# MB_ANALOG.net
KiCad netlist of a schematic drawn in Altium Designer
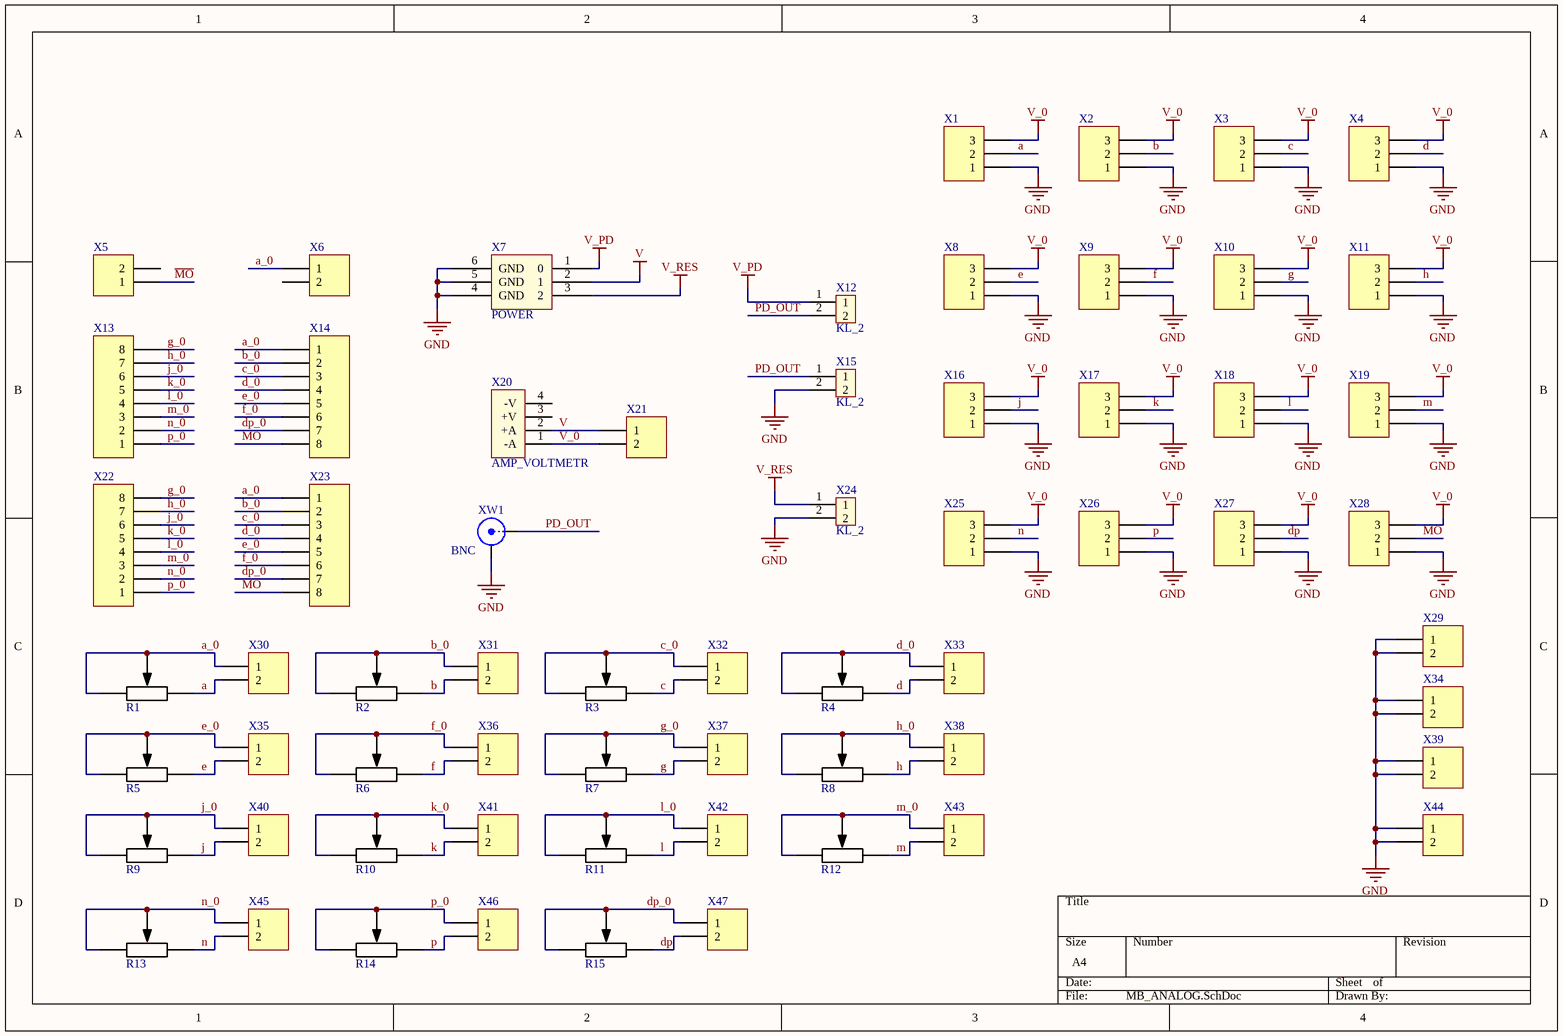
[diagram p0: MB_ANALOG.SchDoc]

(export (version "E")
  (design (tool "Eeschema 10.0.6"))
  (components
    (comp (ref "R1")
      (value "RES 3266W")
      (footprint "RES 3266W")
      (libsource (lib "msp_SchLib") (part "RES 3266W"))
    )
    (comp (ref "R2")
      (value "RES 3266W")
      (footprint "RES 3266W")
      (libsource (lib "msp_SchLib") (part "RES 3266W"))
    )
    (comp (ref "R3")
      (value "RES 3266W")
      (footprint "RES 3266W")
      (libsource (lib "msp_SchLib") (part "RES 3266W"))
    )
    (comp (ref "R4")
      (value "RES 3266W")
      (footprint "RES 3266W")
      (libsource (lib "msp_SchLib") (part "RES 3266W"))
    )
    (comp (ref "R5")
      (value "RES 3266W")
      (footprint "RES 3266W")
      (libsource (lib "msp_SchLib") (part "RES 3266W"))
    )
    (comp (ref "R6")
      (value "RES 3266W")
      (footprint "RES 3266W")
      (libsource (lib "msp_SchLib") (part "RES 3266W"))
    )
    (comp (ref "R7")
      (value "RES 3266W")
      (footprint "RES 3266W")
      (libsource (lib "msp_SchLib") (part "RES 3266W"))
    )
    (comp (ref "R8")
      (value "RES 3266W")
      (footprint "RES 3266W")
      (libsource (lib "msp_SchLib") (part "RES 3266W"))
    )
    (comp (ref "R9")
      (value "RES 3266W")
      (footprint "RES 3266W")
      (libsource (lib "msp_SchLib") (part "RES 3266W"))
    )
    (comp (ref "R10")
      (value "RES 3266W")
      (footprint "RES 3266W")
      (libsource (lib "msp_SchLib") (part "RES 3266W"))
    )
    (comp (ref "R11")
      (value "RES 3266W")
      (footprint "RES 3266W")
      (libsource (lib "msp_SchLib") (part "RES 3266W"))
    )
    (comp (ref "R12")
      (value "RES 3266W")
      (footprint "RES 3266W")
      (libsource (lib "msp_SchLib") (part "RES 3266W"))
    )
    (comp (ref "R13")
      (value "RES 3266W")
      (footprint "RES 3266W")
      (libsource (lib "msp_SchLib") (part "RES 3266W"))
    )
    (comp (ref "R14")
      (value "RES 3266W")
      (footprint "RES 3266W")
      (libsource (lib "msp_SchLib") (part "RES 3266W"))
    )
    (comp (ref "R15")
      (value "RES 3266W")
      (footprint "RES 3266W")
      (libsource (lib "msp_SchLib") (part "RES 3266W"))
    )
    (comp (ref "X1")
      (value "Header 3")
      (footprint "HDR1X3")
      (description "Header, 3-Pin")
      (fields (field (name "PUBLISHER") "Altium Limited"))
      (libsource (lib "Miscellaneous Connectors") (part "Header 3"))
    )
    (comp (ref "X2")
      (value "Header 3")
      (footprint "HDR1X3")
      (description "Header, 3-Pin")
      (fields (field (name "PUBLISHER") "Altium Limited"))
      (libsource (lib "Miscellaneous Connectors") (part "Header 3"))
    )
    (comp (ref "X3")
      (value "Header 3")
      (footprint "HDR1X3")
      (description "Header, 3-Pin")
      (fields (field (name "PUBLISHER") "Altium Limited"))
      (libsource (lib "Miscellaneous Connectors") (part "Header 3"))
    )
    (comp (ref "X4")
      (value "Header 3")
      (footprint "HDR1X3")
      (description "Header, 3-Pin")
      (fields (field (name "PUBLISHER") "Altium Limited"))
      (libsource (lib "Miscellaneous Connectors") (part "Header 3"))
    )
    (comp (ref "X5")
      (value "Header 2")
      (footprint "HDR1X2")
      (description "Header, 2-Pin")
      (fields (field (name "PUBLISHER") "Altium Limited"))
      (libsource (lib "") (part "Header 2_1"))
    )
    (comp (ref "X6")
      (value "Header 2")
      (footprint "HDR1X2")
      (description "Header, 2-Pin")
      (fields (field (name "PUBLISHER") "Altium Limited"))
      (libsource (lib "Miscellaneous Connectors") (part "Header 2"))
    )
    (comp (ref "X7") (value "POWER") (footprint "POWER") (libsource (lib "msp_SchLib") (part "POWER")))
    (comp (ref "X8")
      (value "Header 3")
      (footprint "HDR1X3")
      (description "Header, 3-Pin")
      (fields (field (name "PUBLISHER") "Altium Limited"))
      (libsource (lib "Miscellaneous Connectors") (part "Header 3"))
    )
    (comp (ref "X9")
      (value "Header 3")
      (footprint "HDR1X3")
      (description "Header, 3-Pin")
      (fields (field (name "PUBLISHER") "Altium Limited"))
      (libsource (lib "Miscellaneous Connectors") (part "Header 3"))
    )
    (comp (ref "X10")
      (value "Header 3")
      (footprint "HDR1X3")
      (description "Header, 3-Pin")
      (fields (field (name "PUBLISHER") "Altium Limited"))
      (libsource (lib "Miscellaneous Connectors") (part "Header 3"))
    )
    (comp (ref "X11")
      (value "Header 3")
      (footprint "HDR1X3")
      (description "Header, 3-Pin")
      (fields (field (name "PUBLISHER") "Altium Limited"))
      (libsource (lib "Miscellaneous Connectors") (part "Header 3"))
    )
    (comp (ref "X12")
      (value "KL_2")
      (footprint "KLEMMNIK_2")
      (libsource (lib "vpl_Schlib") (part "KLEMMNIK_2"))
    )
    (comp (ref "X13")
      (value "Header 8")
      (footprint "HDR1X8")
      (description "Header, 8-Pin")
      (fields (field (name "PUBLISHER") "Altium Limited"))
      (libsource (lib "") (part "Header 8_1"))
    )
    (comp (ref "X14")
      (value "Header 8")
      (footprint "HDR1X8")
      (description "Header, 8-Pin")
      (fields (field (name "PUBLISHER") "Altium Limited"))
      (libsource (lib "Miscellaneous Connectors") (part "Header 8"))
    )
    (comp (ref "X15")
      (value "KL_2")
      (footprint "KLEMMNIK_2")
      (libsource (lib "vpl_Schlib") (part "KLEMMNIK_2"))
    )
    (comp (ref "X16")
      (value "Header 3")
      (footprint "HDR1X3")
      (description "Header, 3-Pin")
      (fields (field (name "PUBLISHER") "Altium Limited"))
      (libsource (lib "Miscellaneous Connectors") (part "Header 3"))
    )
    (comp (ref "X17")
      (value "Header 3")
      (footprint "HDR1X3")
      (description "Header, 3-Pin")
      (fields (field (name "PUBLISHER") "Altium Limited"))
      (libsource (lib "Miscellaneous Connectors") (part "Header 3"))
    )
    (comp (ref "X18")
      (value "Header 3")
      (footprint "HDR1X3")
      (description "Header, 3-Pin")
      (fields (field (name "PUBLISHER") "Altium Limited"))
      (libsource (lib "Miscellaneous Connectors") (part "Header 3"))
    )
    (comp (ref "X19")
      (value "Header 3")
      (footprint "HDR1X3")
      (description "Header, 3-Pin")
      (fields (field (name "PUBLISHER") "Altium Limited"))
      (libsource (lib "Miscellaneous Connectors") (part "Header 3"))
    )
    (comp (ref "X20")
      (value "AMP_VOLTMETR")
      (footprint "AMP_VOLTMETR")
      (libsource (lib "msp_SchLib") (part "AMP_VOLTMETR"))
    )
    (comp (ref "X21")
      (value "Header 2")
      (footprint "HDR1X2")
      (description "Header, 2-Pin")
      (fields (field (name "PUBLISHER") "Altium Limited"))
      (libsource (lib "Miscellaneous Connectors") (part "Header 2"))
    )
    (comp (ref "X22")
      (value "Header 8")
      (footprint "HDR1X8")
      (description "Header, 8-Pin")
      (fields (field (name "PUBLISHER") "Altium Limited"))
      (libsource (lib "") (part "Header 8_1"))
    )
    (comp (ref "X23")
      (value "Header 8")
      (footprint "HDR1X8")
      (description "Header, 8-Pin")
      (fields (field (name "PUBLISHER") "Altium Limited"))
      (libsource (lib "Miscellaneous Connectors") (part "Header 8"))
    )
    (comp (ref "X24")
      (value "KL_2")
      (footprint "KLEMMNIK_2")
      (libsource (lib "vpl_Schlib") (part "KLEMMNIK_2"))
    )
    (comp (ref "X25")
      (value "Header 3")
      (footprint "HDR1X3")
      (description "Header, 3-Pin")
      (fields (field (name "PUBLISHER") "Altium Limited"))
      (libsource (lib "Miscellaneous Connectors") (part "Header 3"))
    )
    (comp (ref "X26")
      (value "Header 3")
      (footprint "HDR1X3")
      (description "Header, 3-Pin")
      (fields (field (name "PUBLISHER") "Altium Limited"))
      (libsource (lib "Miscellaneous Connectors") (part "Header 3"))
    )
    (comp (ref "X27")
      (value "Header 3")
      (footprint "HDR1X3")
      (description "Header, 3-Pin")
      (fields (field (name "PUBLISHER") "Altium Limited"))
      (libsource (lib "Miscellaneous Connectors") (part "Header 3"))
    )
    (comp (ref "X28")
      (value "Header 3")
      (footprint "HDR1X3")
      (description "Header, 3-Pin")
      (fields (field (name "PUBLISHER") "Altium Limited"))
      (libsource (lib "Miscellaneous Connectors") (part "Header 3"))
    )
    (comp (ref "X29")
      (value "Header 2")
      (footprint "HDR1X2")
      (description "Header, 2-Pin")
      (fields (field (name "PUBLISHER") "Altium Limited"))
      (libsource (lib "Miscellaneous Connectors") (part "Header 2"))
    )
    (comp (ref "X30")
      (value "Header 2")
      (footprint "HDR1X2")
      (description "Header, 2-Pin")
      (fields (field (name "PUBLISHER") "Altium Limited"))
      (libsource (lib "Miscellaneous Connectors") (part "Header 2"))
    )
    (comp (ref "X31")
      (value "Header 2")
      (footprint "HDR1X2")
      (description "Header, 2-Pin")
      (fields (field (name "PUBLISHER") "Altium Limited"))
      (libsource (lib "Miscellaneous Connectors") (part "Header 2"))
    )
    (comp (ref "X32")
      (value "Header 2")
      (footprint "HDR1X2")
      (description "Header, 2-Pin")
      (fields (field (name "PUBLISHER") "Altium Limited"))
      (libsource (lib "Miscellaneous Connectors") (part "Header 2"))
    )
    (comp (ref "X33")
      (value "Header 2")
      (footprint "HDR1X2")
      (description "Header, 2-Pin")
      (fields (field (name "PUBLISHER") "Altium Limited"))
      (libsource (lib "Miscellaneous Connectors") (part "Header 2"))
    )
    (comp (ref "X34")
      (value "Header 2")
      (footprint "HDR1X2")
      (description "Header, 2-Pin")
      (fields (field (name "PUBLISHER") "Altium Limited"))
      (libsource (lib "Miscellaneous Connectors") (part "Header 2"))
    )
    (comp (ref "X35")
      (value "Header 2")
      (footprint "HDR1X2")
      (description "Header, 2-Pin")
      (fields (field (name "PUBLISHER") "Altium Limited"))
      (libsource (lib "Miscellaneous Connectors") (part "Header 2"))
    )
    (comp (ref "X36")
      (value "Header 2")
      (footprint "HDR1X2")
      (description "Header, 2-Pin")
      (fields (field (name "PUBLISHER") "Altium Limited"))
      (libsource (lib "Miscellaneous Connectors") (part "Header 2"))
    )
    (comp (ref "X37")
      (value "Header 2")
      (footprint "HDR1X2")
      (description "Header, 2-Pin")
      (fields (field (name "PUBLISHER") "Altium Limited"))
      (libsource (lib "Miscellaneous Connectors") (part "Header 2"))
    )
    (comp (ref "X38")
      (value "Header 2")
      (footprint "HDR1X2")
      (description "Header, 2-Pin")
      (fields (field (name "PUBLISHER") "Altium Limited"))
      (libsource (lib "Miscellaneous Connectors") (part "Header 2"))
    )
    (comp (ref "X39")
      (value "Header 2")
      (footprint "HDR1X2")
      (description "Header, 2-Pin")
      (fields (field (name "PUBLISHER") "Altium Limited"))
      (libsource (lib "Miscellaneous Connectors") (part "Header 2"))
    )
    (comp (ref "X40")
      (value "Header 2")
      (footprint "HDR1X2")
      (description "Header, 2-Pin")
      (fields (field (name "PUBLISHER") "Altium Limited"))
      (libsource (lib "Miscellaneous Connectors") (part "Header 2"))
    )
    (comp (ref "X41")
      (value "Header 2")
      (footprint "HDR1X2")
      (description "Header, 2-Pin")
      (fields (field (name "PUBLISHER") "Altium Limited"))
      (libsource (lib "Miscellaneous Connectors") (part "Header 2"))
    )
    (comp (ref "X42")
      (value "Header 2")
      (footprint "HDR1X2")
      (description "Header, 2-Pin")
      (fields (field (name "PUBLISHER") "Altium Limited"))
      (libsource (lib "Miscellaneous Connectors") (part "Header 2"))
    )
    (comp (ref "X43")
      (value "Header 2")
      (footprint "HDR1X2")
      (description "Header, 2-Pin")
      (fields (field (name "PUBLISHER") "Altium Limited"))
      (libsource (lib "Miscellaneous Connectors") (part "Header 2"))
    )
    (comp (ref "X44")
      (value "Header 2")
      (footprint "HDR1X2")
      (description "Header, 2-Pin")
      (fields (field (name "PUBLISHER") "Altium Limited"))
      (libsource (lib "Miscellaneous Connectors") (part "Header 2"))
    )
    (comp (ref "X45")
      (value "Header 2")
      (footprint "HDR1X2")
      (description "Header, 2-Pin")
      (fields (field (name "PUBLISHER") "Altium Limited"))
      (libsource (lib "Miscellaneous Connectors") (part "Header 2"))
    )
    (comp (ref "X46")
      (value "Header 2")
      (footprint "HDR1X2")
      (description "Header, 2-Pin")
      (fields (field (name "PUBLISHER") "Altium Limited"))
      (libsource (lib "Miscellaneous Connectors") (part "Header 2"))
    )
    (comp (ref "X47")
      (value "Header 2")
      (footprint "HDR1X2")
      (description "Header, 2-Pin")
      (fields (field (name "PUBLISHER") "Altium Limited"))
      (libsource (lib "Miscellaneous Connectors") (part "Header 2"))
    )
    (comp (ref "XW1")
      (value "BNC")
      (footprint "BNC_RA CON")
      (description "BNC Elbow Connector")
      (fields (field (name "PUBLISHER") "Altium Limited"))
      (libsource (lib "Miscellaneous Connectors") (part "BNC"))
    )
  )
  (nets
    (net (code "1") (name "/PD_OUT") (class "Default")
      (node (ref "X12") (pin "2") (pinfunction "2_2") (pintype "passive"))
      (node (ref "X15") (pin "1") (pinfunction "1_1") (pintype "passive"))
      (node (ref "XW1") (pin "1") (pinfunction "X_1") (pintype "passive"))
    )
    (net (code "2") (name "/a") (class "Default")
      (node (ref "R1") (pin "3") (pinfunction "3_3") (pintype "passive"))
      (node (ref "X1") (pin "2") (pinfunction "2_2") (pintype "passive"))
      (node (ref "X30") (pin "2") (pinfunction "2_2") (pintype "passive"))
    )
    (net (code "3") (name "/a_0") (class "Default")
      (node (ref "R1") (pin "1") (pinfunction "1_1") (pintype "passive"))
      (node (ref "R1") (pin "2") (pinfunction "2_2") (pintype "passive"))
      (node (ref "X14") (pin "1") (pinfunction "1_1") (pintype "passive"))
      (node (ref "X23") (pin "1") (pinfunction "1_1") (pintype "passive"))
      (node (ref "X30") (pin "1") (pinfunction "1_1") (pintype "passive"))
      (node (ref "X6") (pin "1") (pinfunction "1_1") (pintype "passive"))
    )
    (net (code "4") (name "/b") (class "Default")
      (node (ref "R2") (pin "3") (pinfunction "3_3") (pintype "passive"))
      (node (ref "X2") (pin "2") (pinfunction "2_2") (pintype "passive"))
      (node (ref "X31") (pin "2") (pinfunction "2_2") (pintype "passive"))
    )
    (net (code "5") (name "/b_0") (class "Default")
      (node (ref "R2") (pin "1") (pinfunction "1_1") (pintype "passive"))
      (node (ref "R2") (pin "2") (pinfunction "2_2") (pintype "passive"))
      (node (ref "X14") (pin "2") (pinfunction "2_2") (pintype "passive"))
      (node (ref "X23") (pin "2") (pinfunction "2_2") (pintype "passive"))
      (node (ref "X31") (pin "1") (pinfunction "1_1") (pintype "passive"))
    )
    (net (code "6") (name "/c") (class "Default")
      (node (ref "R3") (pin "3") (pinfunction "3_3") (pintype "passive"))
      (node (ref "X3") (pin "2") (pinfunction "2_2") (pintype "passive"))
      (node (ref "X32") (pin "2") (pinfunction "2_2") (pintype "passive"))
    )
    (net (code "7") (name "/c_0") (class "Default")
      (node (ref "R3") (pin "1") (pinfunction "1_1") (pintype "passive"))
      (node (ref "R3") (pin "2") (pinfunction "2_2") (pintype "passive"))
      (node (ref "X14") (pin "3") (pinfunction "3_3") (pintype "passive"))
      (node (ref "X23") (pin "3") (pinfunction "3_3") (pintype "passive"))
      (node (ref "X32") (pin "1") (pinfunction "1_1") (pintype "passive"))
    )
    (net (code "8") (name "/d") (class "Default")
      (node (ref "R4") (pin "3") (pinfunction "3_3") (pintype "passive"))
      (node (ref "X33") (pin "2") (pinfunction "2_2") (pintype "passive"))
      (node (ref "X4") (pin "2") (pinfunction "2_2") (pintype "passive"))
    )
    (net (code "9") (name "/d_0") (class "Default")
      (node (ref "R4") (pin "1") (pinfunction "1_1") (pintype "passive"))
      (node (ref "R4") (pin "2") (pinfunction "2_2") (pintype "passive"))
      (node (ref "X14") (pin "4") (pinfunction "4_4") (pintype "passive"))
      (node (ref "X23") (pin "4") (pinfunction "4_4") (pintype "passive"))
      (node (ref "X33") (pin "1") (pinfunction "1_1") (pintype "passive"))
    )
    (net (code "10") (name "/dp") (class "Default")
      (node (ref "R15") (pin "3") (pinfunction "3_3") (pintype "passive"))
      (node (ref "X27") (pin "2") (pinfunction "2_2") (pintype "passive"))
      (node (ref "X47") (pin "2") (pinfunction "2_2") (pintype "passive"))
    )
    (net (code "11") (name "/dp_0") (class "Default")
      (node (ref "R15") (pin "1") (pinfunction "1_1") (pintype "passive"))
      (node (ref "R15") (pin "2") (pinfunction "2_2") (pintype "passive"))
      (node (ref "X14") (pin "7") (pinfunction "7_7") (pintype "passive"))
      (node (ref "X23") (pin "7") (pinfunction "7_7") (pintype "passive"))
      (node (ref "X47") (pin "1") (pinfunction "1_1") (pintype "passive"))
    )
    (net (code "12") (name "/e") (class "Default")
      (node (ref "R5") (pin "3") (pinfunction "3_3") (pintype "passive"))
      (node (ref "X35") (pin "2") (pinfunction "2_2") (pintype "passive"))
      (node (ref "X8") (pin "2") (pinfunction "2_2") (pintype "passive"))
    )
    (net (code "13") (name "/e_0") (class "Default")
      (node (ref "R5") (pin "1") (pinfunction "1_1") (pintype "passive"))
      (node (ref "R5") (pin "2") (pinfunction "2_2") (pintype "passive"))
      (node (ref "X14") (pin "5") (pinfunction "5_5") (pintype "passive"))
      (node (ref "X23") (pin "5") (pinfunction "5_5") (pintype "passive"))
      (node (ref "X35") (pin "1") (pinfunction "1_1") (pintype "passive"))
    )
    (net (code "14") (name "/f") (class "Default")
      (node (ref "R6") (pin "3") (pinfunction "3_3") (pintype "passive"))
      (node (ref "X36") (pin "2") (pinfunction "2_2") (pintype "passive"))
      (node (ref "X9") (pin "2") (pinfunction "2_2") (pintype "passive"))
    )
    (net (code "15") (name "/f_0") (class "Default")
      (node (ref "R6") (pin "1") (pinfunction "1_1") (pintype "passive"))
      (node (ref "R6") (pin "2") (pinfunction "2_2") (pintype "passive"))
      (node (ref "X14") (pin "6") (pinfunction "6_6") (pintype "passive"))
      (node (ref "X23") (pin "6") (pinfunction "6_6") (pintype "passive"))
      (node (ref "X36") (pin "1") (pinfunction "1_1") (pintype "passive"))
    )
    (net (code "16") (name "/g") (class "Default")
      (node (ref "R7") (pin "3") (pinfunction "3_3") (pintype "passive"))
      (node (ref "X10") (pin "2") (pinfunction "2_2") (pintype "passive"))
      (node (ref "X37") (pin "2") (pinfunction "2_2") (pintype "passive"))
    )
    (net (code "17") (name "/g_0") (class "Default")
      (node (ref "R7") (pin "1") (pinfunction "1_1") (pintype "passive"))
      (node (ref "R7") (pin "2") (pinfunction "2_2") (pintype "passive"))
      (node (ref "X13") (pin "8") (pinfunction "8_8") (pintype "passive"))
      (node (ref "X22") (pin "8") (pinfunction "8_8") (pintype "passive"))
      (node (ref "X37") (pin "1") (pinfunction "1_1") (pintype "passive"))
    )
    (net (code "18") (name "/h") (class "Default")
      (node (ref "R8") (pin "3") (pinfunction "3_3") (pintype "passive"))
      (node (ref "X11") (pin "2") (pinfunction "2_2") (pintype "passive"))
      (node (ref "X38") (pin "2") (pinfunction "2_2") (pintype "passive"))
    )
    (net (code "19") (name "/h_0") (class "Default")
      (node (ref "R8") (pin "1") (pinfunction "1_1") (pintype "passive"))
      (node (ref "R8") (pin "2") (pinfunction "2_2") (pintype "passive"))
      (node (ref "X13") (pin "7") (pinfunction "7_7") (pintype "passive"))
      (node (ref "X22") (pin "7") (pinfunction "7_7") (pintype "passive"))
      (node (ref "X38") (pin "1") (pinfunction "1_1") (pintype "passive"))
    )
    (net (code "20") (name "/j") (class "Default")
      (node (ref "R9") (pin "3") (pinfunction "3_3") (pintype "passive"))
      (node (ref "X16") (pin "2") (pinfunction "2_2") (pintype "passive"))
      (node (ref "X40") (pin "2") (pinfunction "2_2") (pintype "passive"))
    )
    (net (code "21") (name "/j_0") (class "Default")
      (node (ref "R9") (pin "1") (pinfunction "1_1") (pintype "passive"))
      (node (ref "R9") (pin "2") (pinfunction "2_2") (pintype "passive"))
      (node (ref "X13") (pin "6") (pinfunction "6_6") (pintype "passive"))
      (node (ref "X22") (pin "6") (pinfunction "6_6") (pintype "passive"))
      (node (ref "X40") (pin "1") (pinfunction "1_1") (pintype "passive"))
    )
    (net (code "22") (name "/k") (class "Default")
      (node (ref "R10") (pin "3") (pinfunction "3_3") (pintype "passive"))
      (node (ref "X17") (pin "2") (pinfunction "2_2") (pintype "passive"))
      (node (ref "X41") (pin "2") (pinfunction "2_2") (pintype "passive"))
    )
    (net (code "23") (name "/k_0") (class "Default")
      (node (ref "R10") (pin "1") (pinfunction "1_1") (pintype "passive"))
      (node (ref "R10") (pin "2") (pinfunction "2_2") (pintype "passive"))
      (node (ref "X13") (pin "5") (pinfunction "5_5") (pintype "passive"))
      (node (ref "X22") (pin "5") (pinfunction "5_5") (pintype "passive"))
      (node (ref "X41") (pin "1") (pinfunction "1_1") (pintype "passive"))
    )
    (net (code "24") (name "/l") (class "Default")
      (node (ref "R11") (pin "3") (pinfunction "3_3") (pintype "passive"))
      (node (ref "X18") (pin "2") (pinfunction "2_2") (pintype "passive"))
      (node (ref "X42") (pin "2") (pinfunction "2_2") (pintype "passive"))
    )
    (net (code "25") (name "/l_0") (class "Default")
      (node (ref "R11") (pin "1") (pinfunction "1_1") (pintype "passive"))
      (node (ref "R11") (pin "2") (pinfunction "2_2") (pintype "passive"))
      (node (ref "X13") (pin "4") (pinfunction "4_4") (pintype "passive"))
      (node (ref "X22") (pin "4") (pinfunction "4_4") (pintype "passive"))
      (node (ref "X42") (pin "1") (pinfunction "1_1") (pintype "passive"))
    )
    (net (code "26") (name "/m") (class "Default")
      (node (ref "R12") (pin "3") (pinfunction "3_3") (pintype "passive"))
      (node (ref "X19") (pin "2") (pinfunction "2_2") (pintype "passive"))
      (node (ref "X43") (pin "2") (pinfunction "2_2") (pintype "passive"))
    )
    (net (code "27") (name "/m_0") (class "Default")
      (node (ref "R12") (pin "1") (pinfunction "1_1") (pintype "passive"))
      (node (ref "R12") (pin "2") (pinfunction "2_2") (pintype "passive"))
      (node (ref "X13") (pin "3") (pinfunction "3_3") (pintype "passive"))
      (node (ref "X22") (pin "3") (pinfunction "3_3") (pintype "passive"))
      (node (ref "X43") (pin "1") (pinfunction "1_1") (pintype "passive"))
    )
    (net (code "28") (name "/n") (class "Default")
      (node (ref "R13") (pin "3") (pinfunction "3_3") (pintype "passive"))
      (node (ref "X25") (pin "2") (pinfunction "2_2") (pintype "passive"))
      (node (ref "X45") (pin "2") (pinfunction "2_2") (pintype "passive"))
    )
    (net (code "29") (name "/n_0") (class "Default")
      (node (ref "R13") (pin "1") (pinfunction "1_1") (pintype "passive"))
      (node (ref "R13") (pin "2") (pinfunction "2_2") (pintype "passive"))
      (node (ref "X13") (pin "2") (pinfunction "2_2") (pintype "passive"))
      (node (ref "X22") (pin "2") (pinfunction "2_2") (pintype "passive"))
      (node (ref "X45") (pin "1") (pinfunction "1_1") (pintype "passive"))
    )
    (net (code "30") (name "/p") (class "Default")
      (node (ref "R14") (pin "3") (pinfunction "3_3") (pintype "passive"))
      (node (ref "X26") (pin "2") (pinfunction "2_2") (pintype "passive"))
      (node (ref "X46") (pin "2") (pinfunction "2_2") (pintype "passive"))
    )
    (net (code "31") (name "/p_0") (class "Default")
      (node (ref "R14") (pin "1") (pinfunction "1_1") (pintype "passive"))
      (node (ref "R14") (pin "2") (pinfunction "2_2") (pintype "passive"))
      (node (ref "X13") (pin "1") (pinfunction "1_1") (pintype "passive"))
      (node (ref "X22") (pin "1") (pinfunction "1_1") (pintype "passive"))
      (node (ref "X46") (pin "1") (pinfunction "1_1") (pintype "passive"))
    )
    (net (code "32") (name "/~{MO}") (class "Default")
      (node (ref "X14") (pin "8") (pinfunction "8_8") (pintype "passive"))
      (node (ref "X23") (pin "8") (pinfunction "8_8") (pintype "passive"))
      (node (ref "X28") (pin "2") (pinfunction "2_2") (pintype "passive"))
      (node (ref "X5") (pin "1") (pinfunction "1_1") (pintype "passive"))
    )
    (net (code "33") (name "GND") (class "Default")
      (node (ref "X1") (pin "1") (pinfunction "1_1") (pintype "passive"))
      (node (ref "X10") (pin "1") (pinfunction "1_1") (pintype "passive"))
      (node (ref "X11") (pin "1") (pinfunction "1_1") (pintype "passive"))
      (node (ref "X15") (pin "2") (pinfunction "2_2") (pintype "passive"))
      (node (ref "X16") (pin "1") (pinfunction "1_1") (pintype "passive"))
      (node (ref "X17") (pin "1") (pinfunction "1_1") (pintype "passive"))
      (node (ref "X18") (pin "1") (pinfunction "1_1") (pintype "passive"))
      (node (ref "X19") (pin "1") (pinfunction "1_1") (pintype "passive"))
      (node (ref "X2") (pin "1") (pinfunction "1_1") (pintype "passive"))
      (node (ref "X24") (pin "2") (pinfunction "2_2") (pintype "passive"))
      (node (ref "X25") (pin "1") (pinfunction "1_1") (pintype "passive"))
      (node (ref "X26") (pin "1") (pinfunction "1_1") (pintype "passive"))
      (node (ref "X27") (pin "1") (pinfunction "1_1") (pintype "passive"))
      (node (ref "X28") (pin "1") (pinfunction "1_1") (pintype "passive"))
      (node (ref "X29") (pin "1") (pinfunction "1_1") (pintype "passive"))
      (node (ref "X29") (pin "2") (pinfunction "2_2") (pintype "passive"))
      (node (ref "X3") (pin "1") (pinfunction "1_1") (pintype "passive"))
      (node (ref "X34") (pin "1") (pinfunction "1_1") (pintype "passive"))
      (node (ref "X34") (pin "2") (pinfunction "2_2") (pintype "passive"))
      (node (ref "X39") (pin "1") (pinfunction "1_1") (pintype "passive"))
      (node (ref "X39") (pin "2") (pinfunction "2_2") (pintype "passive"))
      (node (ref "X4") (pin "1") (pinfunction "1_1") (pintype "passive"))
      (node (ref "X44") (pin "1") (pinfunction "1_1") (pintype "passive"))
      (node (ref "X44") (pin "2") (pinfunction "2_2") (pintype "passive"))
      (node (ref "X7") (pin "4") (pinfunction "GND_4") (pintype "passive"))
      (node (ref "X7") (pin "5") (pinfunction "GND_5") (pintype "passive"))
      (node (ref "X7") (pin "6") (pinfunction "GND_6") (pintype "passive"))
      (node (ref "X8") (pin "1") (pinfunction "1_1") (pintype "passive"))
      (node (ref "X9") (pin "1") (pinfunction "1_1") (pintype "passive"))
      (node (ref "XW1") (pin "2") (pinfunction "Y_2") (pintype "passive"))
    )
    (net (code "34") (name "V") (class "Default")
      (node (ref "X20") (pin "2") (pinfunction "+A_2") (pintype "passive"))
      (node (ref "X21") (pin "1") (pinfunction "1_1") (pintype "passive"))
      (node (ref "X7") (pin "2") (pinfunction "1_2") (pintype "passive"))
    )
    (net (code "35") (name "V_0") (class "Default")
      (node (ref "X1") (pin "3") (pinfunction "3_3") (pintype "passive"))
      (node (ref "X10") (pin "3") (pinfunction "3_3") (pintype "passive"))
      (node (ref "X11") (pin "3") (pinfunction "3_3") (pintype "passive"))
      (node (ref "X16") (pin "3") (pinfunction "3_3") (pintype "passive"))
      (node (ref "X17") (pin "3") (pinfunction "3_3") (pintype "passive"))
      (node (ref "X18") (pin "3") (pinfunction "3_3") (pintype "passive"))
      (node (ref "X19") (pin "3") (pinfunction "3_3") (pintype "passive"))
      (node (ref "X2") (pin "3") (pinfunction "3_3") (pintype "passive"))
      (node (ref "X20") (pin "1") (pinfunction "-A_1") (pintype "passive"))
      (node (ref "X21") (pin "2") (pinfunction "2_2") (pintype "passive"))
      (node (ref "X25") (pin "3") (pinfunction "3_3") (pintype "passive"))
      (node (ref "X26") (pin "3") (pinfunction "3_3") (pintype "passive"))
      (node (ref "X27") (pin "3") (pinfunction "3_3") (pintype "passive"))
      (node (ref "X28") (pin "3") (pinfunction "3_3") (pintype "passive"))
      (node (ref "X3") (pin "3") (pinfunction "3_3") (pintype "passive"))
      (node (ref "X4") (pin "3") (pinfunction "3_3") (pintype "passive"))
      (node (ref "X8") (pin "3") (pinfunction "3_3") (pintype "passive"))
      (node (ref "X9") (pin "3") (pinfunction "3_3") (pintype "passive"))
    )
    (net (code "36") (name "V_PD") (class "Default")
      (node (ref "X12") (pin "1") (pinfunction "1_1") (pintype "passive"))
      (node (ref "X7") (pin "1") (pinfunction "0_1") (pintype "passive"))
    )
    (net (code "37") (name "V_RES") (class "Default")
      (node (ref "X24") (pin "1") (pinfunction "1_1") (pintype "passive"))
      (node (ref "X7") (pin "3") (pinfunction "2_3") (pintype "passive"))
    )
    (net (code "38") (name "unconnected-(X5-Pad2)") (class "Default")
      (node (ref "X5") (pin "2") (pinfunction "2_2") (pintype "passive"))
    )
    (net (code "39") (name "unconnected-(X6-Pad2)") (class "Default")
      (node (ref "X6") (pin "2") (pinfunction "2_2") (pintype "passive"))
    )
    (net (code "40") (name "unconnected-(X20-+V-Pad3)") (class "Default")
      (node (ref "X20") (pin "3") (pinfunction "+V_3") (pintype "passive"))
    )
    (net (code "41") (name "unconnected-(X20--V-Pad4)") (class "Default")
      (node (ref "X20") (pin "4") (pinfunction "-V_4") (pintype "passive"))
    )
  )
)
